# Hand_Sensors.net
KiCad netlist of a schematic drawn in Altium Designer
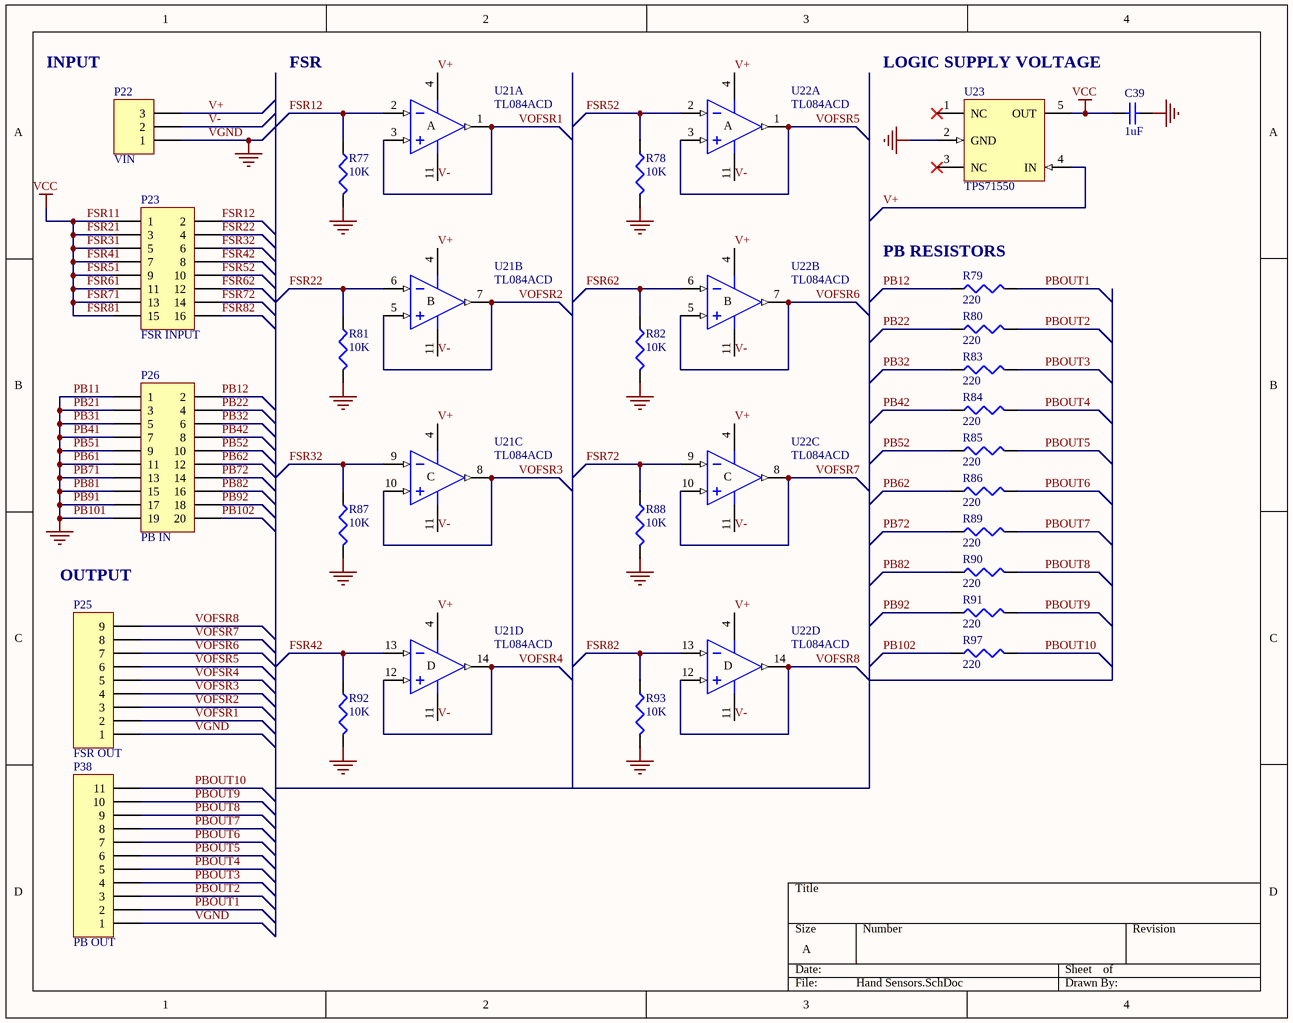
[diagram p0: Hand Sensors.SchDoc]

(export (version "E")
  (design (tool "Eeschema 10.0.6"))
  (components
    (comp (ref "C39")
      (value "1uF")
      (footprint "CAPC2012M")
      (description "Capacitor (Semiconductor SIM Model)")
      (fields (field (name "Comment") "Cap Semi") (field (name "PUBLISHER") "Altium Limited"))
      (libsource (lib "Miscellaneous Devices") (part "Cap Semi"))
    )
    (comp (ref "P22")
      (value "VIN")
      (footprint "AZUL5-3")
      (description "Header, 3-Pin")
      (fields (field (name "PUBLISHER") "Altium Limited"))
      (libsource (lib "Miscellaneous Connectors") (part "Header 3"))
    )
    (comp (ref "P23")
      (value "FSR INPUT")
      (footprint "HDR2X8")
      (description "Header, 8-Pin, Dual row")
      (fields (field (name "PUBLISHER") "Altium Limited"))
      (libsource (lib "Miscellaneous Connectors") (part "Header 8X2"))
    )
    (comp (ref "P25")
      (value "FSR OUT")
      (footprint "HDR1X9H")
      (description "Header, 9-Pin, Right Angle")
      (fields (field (name "PUBLISHER") "Altium Limited"))
      (libsource (lib "Miscellaneous Connectors") (part "Header 9H"))
    )
    (comp (ref "P26")
      (value "PB IN")
      (footprint "HDR2X10")
      (description "Header, 10-Pin, Dual row")
      (fields (field (name "PUBLISHER") "Altium Limited"))
      (libsource (lib "Miscellaneous Connectors") (part "Header 10X2"))
    )
    (comp (ref "P38")
      (value "PB OUT")
      (footprint "HDR1X11H")
      (description "Header, 11-Pin, Right Angle")
      (fields (field (name "PUBLISHER") "Altium Limited"))
      (libsource (lib "Miscellaneous Connectors") (part "Header 11H"))
    )
    (comp (ref "R77")
      (value "10K")
      (footprint "RESC3225M")
      (description "Resistor")
      (fields (field (name "Comment") "Res3") (field (name "PUBLISHER") "Altium Limited"))
      (libsource (lib "Miscellaneous Devices") (part "Res3"))
    )
    (comp (ref "R78")
      (value "10K")
      (footprint "RESC3225M")
      (description "Resistor")
      (fields (field (name "Comment") "Res3") (field (name "PUBLISHER") "Altium Limited"))
      (libsource (lib "Miscellaneous Devices") (part "Res3"))
    )
    (comp (ref "R79")
      (value "220")
      (footprint "RESC3225M")
      (description "Resistor")
      (fields (field (name "Comment") "Res3") (field (name "PUBLISHER") "Altium Limited"))
      (libsource (lib "Miscellaneous Devices") (part "Res3"))
    )
    (comp (ref "R80")
      (value "220")
      (footprint "RESC3225M")
      (description "Resistor")
      (fields (field (name "Comment") "Res3") (field (name "PUBLISHER") "Altium Limited"))
      (libsource (lib "Miscellaneous Devices") (part "Res3"))
    )
    (comp (ref "R81")
      (value "10K")
      (footprint "RESC3225M")
      (description "Resistor")
      (fields (field (name "Comment") "Res3") (field (name "PUBLISHER") "Altium Limited"))
      (libsource (lib "Miscellaneous Devices") (part "Res3"))
    )
    (comp (ref "R82")
      (value "10K")
      (footprint "RESC3225M")
      (description "Resistor")
      (fields (field (name "Comment") "Res3") (field (name "PUBLISHER") "Altium Limited"))
      (libsource (lib "Miscellaneous Devices") (part "Res3"))
    )
    (comp (ref "R83")
      (value "220")
      (footprint "RESC3225M")
      (description "Resistor")
      (fields (field (name "Comment") "Res3") (field (name "PUBLISHER") "Altium Limited"))
      (libsource (lib "Miscellaneous Devices") (part "Res3"))
    )
    (comp (ref "R84")
      (value "220")
      (footprint "RESC3225M")
      (description "Resistor")
      (fields (field (name "Comment") "Res3") (field (name "PUBLISHER") "Altium Limited"))
      (libsource (lib "Miscellaneous Devices") (part "Res3"))
    )
    (comp (ref "R85")
      (value "220")
      (footprint "RESC3225M")
      (description "Resistor")
      (fields (field (name "Comment") "Res3") (field (name "PUBLISHER") "Altium Limited"))
      (libsource (lib "Miscellaneous Devices") (part "Res3"))
    )
    (comp (ref "R86")
      (value "220")
      (footprint "RESC3225M")
      (description "Resistor")
      (fields (field (name "Comment") "Res3") (field (name "PUBLISHER") "Altium Limited"))
      (libsource (lib "Miscellaneous Devices") (part "Res3"))
    )
    (comp (ref "R87")
      (value "10K")
      (footprint "RESC3225M")
      (description "Resistor")
      (fields (field (name "Comment") "Res3") (field (name "PUBLISHER") "Altium Limited"))
      (libsource (lib "Miscellaneous Devices") (part "Res3"))
    )
    (comp (ref "R88")
      (value "10K")
      (footprint "RESC3225M")
      (description "Resistor")
      (fields (field (name "Comment") "Res3") (field (name "PUBLISHER") "Altium Limited"))
      (libsource (lib "Miscellaneous Devices") (part "Res3"))
    )
    (comp (ref "R89")
      (value "220")
      (footprint "RESC3225M")
      (description "Resistor")
      (fields (field (name "Comment") "Res3") (field (name "PUBLISHER") "Altium Limited"))
      (libsource (lib "Miscellaneous Devices") (part "Res3"))
    )
    (comp (ref "R90")
      (value "220")
      (footprint "RESC3225M")
      (description "Resistor")
      (fields (field (name "Comment") "Res3") (field (name "PUBLISHER") "Altium Limited"))
      (libsource (lib "Miscellaneous Devices") (part "Res3"))
    )
    (comp (ref "R91")
      (value "220")
      (footprint "RESC3225M")
      (description "Resistor")
      (fields (field (name "Comment") "Res3") (field (name "PUBLISHER") "Altium Limited"))
      (libsource (lib "Miscellaneous Devices") (part "Res3"))
    )
    (comp (ref "R92")
      (value "10K")
      (footprint "RESC3225M")
      (description "Resistor")
      (fields (field (name "Comment") "Res3") (field (name "PUBLISHER") "Altium Limited"))
      (libsource (lib "Miscellaneous Devices") (part "Res3"))
    )
    (comp (ref "R93")
      (value "10K")
      (footprint "RESC3225M")
      (description "Resistor")
      (fields (field (name "Comment") "Res3") (field (name "PUBLISHER") "Altium Limited"))
      (libsource (lib "Miscellaneous Devices") (part "Res3"))
    )
    (comp (ref "R97")
      (value "220")
      (footprint "RESC3225M")
      (description "Resistor")
      (fields (field (name "Comment") "Res3") (field (name "PUBLISHER") "Altium Limited"))
      (libsource (lib "Miscellaneous Devices") (part "Res3"))
    )
    (comp (ref "U21")
      (value "TL084ACD")
      (footprint "SO14_N")
      (description "General-Purpose J-FET Quad Operational Amplifier")
      (fields (field (name "PUBLISHER") "Altium Limited"))
      (libsource (lib "ST Operational Amplifier") (part "TL084ACD"))
    )
    (comp (ref "U22")
      (value "TL084ACD")
      (footprint "SO14_N")
      (description "General-Purpose J-FET Quad Operational Amplifier")
      (fields (field (name "PUBLISHER") "Altium Limited"))
      (libsource (lib "ST Operational Amplifier") (part "TL084ACD"))
    )
    (comp (ref "U23")
      (value "TPS71550")
      (footprint "SOT353-5L")
      (libsource (lib "LitoLibrary") (part "TPS71550"))
    )
  )
  (nets
    (net (code "1") (name "/FSR12") (class "Default")
      (node (ref "P23") (pin "2") (pinfunction "2_2") (pintype "passive"))
      (node (ref "R77") (pin "1") (pinfunction "1_1") (pintype "passive"))
      (node (ref "U21") (pin "2") (pinfunction "IN-_2") (pintype "input"))
    )
    (net (code "2") (name "/FSR22") (class "Default")
      (node (ref "P23") (pin "4") (pinfunction "4_4") (pintype "passive"))
      (node (ref "R81") (pin "1") (pinfunction "1_1") (pintype "passive"))
      (node (ref "U21") (pin "6") (pinfunction "IN-_6") (pintype "input"))
    )
    (net (code "3") (name "/FSR32") (class "Default")
      (node (ref "P23") (pin "6") (pinfunction "6_6") (pintype "passive"))
      (node (ref "R87") (pin "1") (pinfunction "1_1") (pintype "passive"))
      (node (ref "U21") (pin "9") (pinfunction "IN-_9") (pintype "input"))
    )
    (net (code "4") (name "/FSR42") (class "Default")
      (node (ref "P23") (pin "8") (pinfunction "8_8") (pintype "passive"))
      (node (ref "R92") (pin "1") (pinfunction "1_1") (pintype "passive"))
      (node (ref "U21") (pin "13") (pinfunction "IN-_13") (pintype "input"))
    )
    (net (code "5") (name "/FSR52") (class "Default")
      (node (ref "P23") (pin "10") (pinfunction "10_10") (pintype "passive"))
      (node (ref "R78") (pin "1") (pinfunction "1_1") (pintype "passive"))
      (node (ref "U22") (pin "2") (pinfunction "IN-_2") (pintype "input"))
    )
    (net (code "6") (name "/FSR62") (class "Default")
      (node (ref "P23") (pin "12") (pinfunction "12_12") (pintype "passive"))
      (node (ref "R82") (pin "1") (pinfunction "1_1") (pintype "passive"))
      (node (ref "U22") (pin "6") (pinfunction "IN-_6") (pintype "input"))
    )
    (net (code "7") (name "/FSR72") (class "Default")
      (node (ref "P23") (pin "14") (pinfunction "14_14") (pintype "passive"))
      (node (ref "R88") (pin "1") (pinfunction "1_1") (pintype "passive"))
      (node (ref "U22") (pin "9") (pinfunction "IN-_9") (pintype "input"))
    )
    (net (code "8") (name "/FSR82") (class "Default")
      (node (ref "P23") (pin "16") (pinfunction "16_16") (pintype "passive"))
      (node (ref "R93") (pin "1") (pinfunction "1_1") (pintype "passive"))
      (node (ref "U22") (pin "13") (pinfunction "IN-_13") (pintype "input"))
    )
    (net (code "9") (name "/PB12") (class "Default")
      (node (ref "P26") (pin "2") (pinfunction "2_2") (pintype "passive"))
      (node (ref "R79") (pin "1") (pinfunction "1_1") (pintype "passive"))
    )
    (net (code "10") (name "/PB22") (class "Default")
      (node (ref "P26") (pin "4") (pinfunction "4_4") (pintype "passive"))
      (node (ref "R80") (pin "1") (pinfunction "1_1") (pintype "passive"))
    )
    (net (code "11") (name "/PB32") (class "Default")
      (node (ref "P26") (pin "6") (pinfunction "6_6") (pintype "passive"))
      (node (ref "R83") (pin "1") (pinfunction "1_1") (pintype "passive"))
    )
    (net (code "12") (name "/PB42") (class "Default")
      (node (ref "P26") (pin "8") (pinfunction "8_8") (pintype "passive"))
      (node (ref "R84") (pin "1") (pinfunction "1_1") (pintype "passive"))
    )
    (net (code "13") (name "/PB52") (class "Default")
      (node (ref "P26") (pin "10") (pinfunction "10_10") (pintype "passive"))
      (node (ref "R85") (pin "1") (pinfunction "1_1") (pintype "passive"))
    )
    (net (code "14") (name "/PB62") (class "Default")
      (node (ref "P26") (pin "12") (pinfunction "12_12") (pintype "passive"))
      (node (ref "R86") (pin "1") (pinfunction "1_1") (pintype "passive"))
    )
    (net (code "15") (name "/PB72") (class "Default")
      (node (ref "P26") (pin "14") (pinfunction "14_14") (pintype "passive"))
      (node (ref "R89") (pin "1") (pinfunction "1_1") (pintype "passive"))
    )
    (net (code "16") (name "/PB82") (class "Default")
      (node (ref "P26") (pin "16") (pinfunction "16_16") (pintype "passive"))
      (node (ref "R90") (pin "1") (pinfunction "1_1") (pintype "passive"))
    )
    (net (code "17") (name "/PB92") (class "Default")
      (node (ref "P26") (pin "18") (pinfunction "18_18") (pintype "passive"))
      (node (ref "R91") (pin "1") (pinfunction "1_1") (pintype "passive"))
    )
    (net (code "18") (name "/PB102") (class "Default")
      (node (ref "P26") (pin "20") (pinfunction "20_20") (pintype "passive"))
      (node (ref "R97") (pin "1") (pinfunction "1_1") (pintype "passive"))
    )
    (net (code "19") (name "/PBOUT1") (class "Default")
      (node (ref "P38") (pin "2") (pinfunction "2_2") (pintype "passive"))
      (node (ref "R79") (pin "2") (pinfunction "2_2") (pintype "passive"))
    )
    (net (code "20") (name "/PBOUT2") (class "Default")
      (node (ref "P38") (pin "3") (pinfunction "3_3") (pintype "passive"))
      (node (ref "R80") (pin "2") (pinfunction "2_2") (pintype "passive"))
    )
    (net (code "21") (name "/PBOUT3") (class "Default")
      (node (ref "P38") (pin "4") (pinfunction "4_4") (pintype "passive"))
      (node (ref "R83") (pin "2") (pinfunction "2_2") (pintype "passive"))
    )
    (net (code "22") (name "/PBOUT4") (class "Default")
      (node (ref "P38") (pin "5") (pinfunction "5_5") (pintype "passive"))
      (node (ref "R84") (pin "2") (pinfunction "2_2") (pintype "passive"))
    )
    (net (code "23") (name "/PBOUT5") (class "Default")
      (node (ref "P38") (pin "6") (pinfunction "6_6") (pintype "passive"))
      (node (ref "R85") (pin "2") (pinfunction "2_2") (pintype "passive"))
    )
    (net (code "24") (name "/PBOUT6") (class "Default")
      (node (ref "P38") (pin "7") (pinfunction "7_7") (pintype "passive"))
      (node (ref "R86") (pin "2") (pinfunction "2_2") (pintype "passive"))
    )
    (net (code "25") (name "/PBOUT7") (class "Default")
      (node (ref "P38") (pin "8") (pinfunction "8_8") (pintype "passive"))
      (node (ref "R89") (pin "2") (pinfunction "2_2") (pintype "passive"))
    )
    (net (code "26") (name "/PBOUT8") (class "Default")
      (node (ref "P38") (pin "9") (pinfunction "9_9") (pintype "passive"))
      (node (ref "R90") (pin "2") (pinfunction "2_2") (pintype "passive"))
    )
    (net (code "27") (name "/PBOUT9") (class "Default")
      (node (ref "P38") (pin "10") (pinfunction "10_10") (pintype "passive"))
      (node (ref "R91") (pin "2") (pinfunction "2_2") (pintype "passive"))
    )
    (net (code "28") (name "/PBOUT10") (class "Default")
      (node (ref "P38") (pin "11") (pinfunction "11_11") (pintype "passive"))
      (node (ref "R97") (pin "2") (pinfunction "2_2") (pintype "passive"))
    )
    (net (code "29") (name "/V+") (class "Default")
      (node (ref "P22") (pin "3") (pinfunction "3_3") (pintype "passive"))
      (node (ref "U21") (pin "4") (pinfunction "V+_4") (pintype "power_in"))
      (node (ref "U22") (pin "4") (pinfunction "V+_4") (pintype "power_in"))
      (node (ref "U23") (pin "4") (pinfunction "IN_4") (pintype "input"))
    )
    (net (code "30") (name "/V-") (class "Default")
      (node (ref "P22") (pin "2") (pinfunction "2_2") (pintype "passive"))
      (node (ref "U21") (pin "11") (pinfunction "V-_11") (pintype "power_in"))
      (node (ref "U22") (pin "11") (pinfunction "V-_11") (pintype "power_in"))
    )
    (net (code "31") (name "/VOFSR1") (class "Default")
      (node (ref "P25") (pin "2") (pinfunction "2_2") (pintype "passive"))
      (node (ref "U21") (pin "1") (pinfunction "OUT_1") (pintype "output"))
      (node (ref "U21") (pin "3") (pinfunction "IN+_3") (pintype "input"))
    )
    (net (code "32") (name "/VOFSR2") (class "Default")
      (node (ref "P25") (pin "3") (pinfunction "3_3") (pintype "passive"))
      (node (ref "U21") (pin "5") (pinfunction "IN+_5") (pintype "input"))
      (node (ref "U21") (pin "7") (pinfunction "OUT_7") (pintype "output"))
    )
    (net (code "33") (name "/VOFSR3") (class "Default")
      (node (ref "P25") (pin "4") (pinfunction "4_4") (pintype "passive"))
      (node (ref "U21") (pin "10") (pinfunction "IN+_10") (pintype "input"))
      (node (ref "U21") (pin "8") (pinfunction "OUT_8") (pintype "output"))
    )
    (net (code "34") (name "/VOFSR4") (class "Default")
      (node (ref "P25") (pin "5") (pinfunction "5_5") (pintype "passive"))
      (node (ref "U21") (pin "12") (pinfunction "IN+_12") (pintype "input"))
      (node (ref "U21") (pin "14") (pinfunction "OUT_14") (pintype "output"))
    )
    (net (code "35") (name "/VOFSR5") (class "Default")
      (node (ref "P25") (pin "6") (pinfunction "6_6") (pintype "passive"))
      (node (ref "U22") (pin "1") (pinfunction "OUT_1") (pintype "output"))
      (node (ref "U22") (pin "3") (pinfunction "IN+_3") (pintype "input"))
    )
    (net (code "36") (name "/VOFSR6") (class "Default")
      (node (ref "P25") (pin "7") (pinfunction "7_7") (pintype "passive"))
      (node (ref "U22") (pin "5") (pinfunction "IN+_5") (pintype "input"))
      (node (ref "U22") (pin "7") (pinfunction "OUT_7") (pintype "output"))
    )
    (net (code "37") (name "/VOFSR7") (class "Default")
      (node (ref "P25") (pin "8") (pinfunction "8_8") (pintype "passive"))
      (node (ref "U22") (pin "10") (pinfunction "IN+_10") (pintype "input"))
      (node (ref "U22") (pin "8") (pinfunction "OUT_8") (pintype "output"))
    )
    (net (code "38") (name "/VOFSR8") (class "Default")
      (node (ref "P25") (pin "9") (pinfunction "9_9") (pintype "passive"))
      (node (ref "U22") (pin "12") (pinfunction "IN+_12") (pintype "input"))
      (node (ref "U22") (pin "14") (pinfunction "OUT_14") (pintype "output"))
    )
    (net (code "39") (name "GND") (class "Default")
      (node (ref "C39") (pin "2") (pinfunction "2_2") (pintype "passive"))
      (node (ref "P22") (pin "1") (pinfunction "1_1") (pintype "passive"))
      (node (ref "P25") (pin "1") (pinfunction "1_1") (pintype "passive"))
      (node (ref "P26") (pin "1") (pinfunction "1_1") (pintype "passive"))
      (node (ref "P26") (pin "11") (pinfunction "11_11") (pintype "passive"))
      (node (ref "P26") (pin "13") (pinfunction "13_13") (pintype "passive"))
      (node (ref "P26") (pin "15") (pinfunction "15_15") (pintype "passive"))
      (node (ref "P26") (pin "17") (pinfunction "17_17") (pintype "passive"))
      (node (ref "P26") (pin "19") (pinfunction "19_19") (pintype "passive"))
      (node (ref "P26") (pin "3") (pinfunction "3_3") (pintype "passive"))
      (node (ref "P26") (pin "5") (pinfunction "5_5") (pintype "passive"))
      (node (ref "P26") (pin "7") (pinfunction "7_7") (pintype "passive"))
      (node (ref "P26") (pin "9") (pinfunction "9_9") (pintype "passive"))
      (node (ref "P38") (pin "1") (pinfunction "1_1") (pintype "passive"))
      (node (ref "R77") (pin "2") (pinfunction "2_2") (pintype "passive"))
      (node (ref "R78") (pin "2") (pinfunction "2_2") (pintype "passive"))
      (node (ref "R81") (pin "2") (pinfunction "2_2") (pintype "passive"))
      (node (ref "R82") (pin "2") (pinfunction "2_2") (pintype "passive"))
      (node (ref "R87") (pin "2") (pinfunction "2_2") (pintype "passive"))
      (node (ref "R88") (pin "2") (pinfunction "2_2") (pintype "passive"))
      (node (ref "R92") (pin "2") (pinfunction "2_2") (pintype "passive"))
      (node (ref "R93") (pin "2") (pinfunction "2_2") (pintype "passive"))
      (node (ref "U23") (pin "2") (pinfunction "GND_2") (pintype "input"))
    )
    (net (code "40") (name "VCC") (class "Default")
      (node (ref "C39") (pin "1") (pinfunction "1_1") (pintype "passive"))
      (node (ref "P23") (pin "1") (pinfunction "1_1") (pintype "passive"))
      (node (ref "P23") (pin "11") (pinfunction "11_11") (pintype "passive"))
      (node (ref "P23") (pin "13") (pinfunction "13_13") (pintype "passive"))
      (node (ref "P23") (pin "15") (pinfunction "15_15") (pintype "passive"))
      (node (ref "P23") (pin "3") (pinfunction "3_3") (pintype "passive"))
      (node (ref "P23") (pin "5") (pinfunction "5_5") (pintype "passive"))
      (node (ref "P23") (pin "7") (pinfunction "7_7") (pintype "passive"))
      (node (ref "P23") (pin "9") (pinfunction "9_9") (pintype "passive"))
      (node (ref "U23") (pin "5") (pinfunction "OUT_5") (pintype "passive"))
    )
    (net (code "41") (name "unconnected-(U23-NC-Pad1)") (class "Default")
      (node (ref "U23") (pin "1") (pinfunction "NC_1") (pintype "passive+no_connect"))
    )
    (net (code "42") (name "unconnected-(U23-NC-Pad3)") (class "Default")
      (node (ref "U23") (pin "3") (pinfunction "NC_3") (pintype "passive+no_connect"))
    )
  )
)
